# Manifold.net
KiCad netlist of a schematic drawn in EAGLE
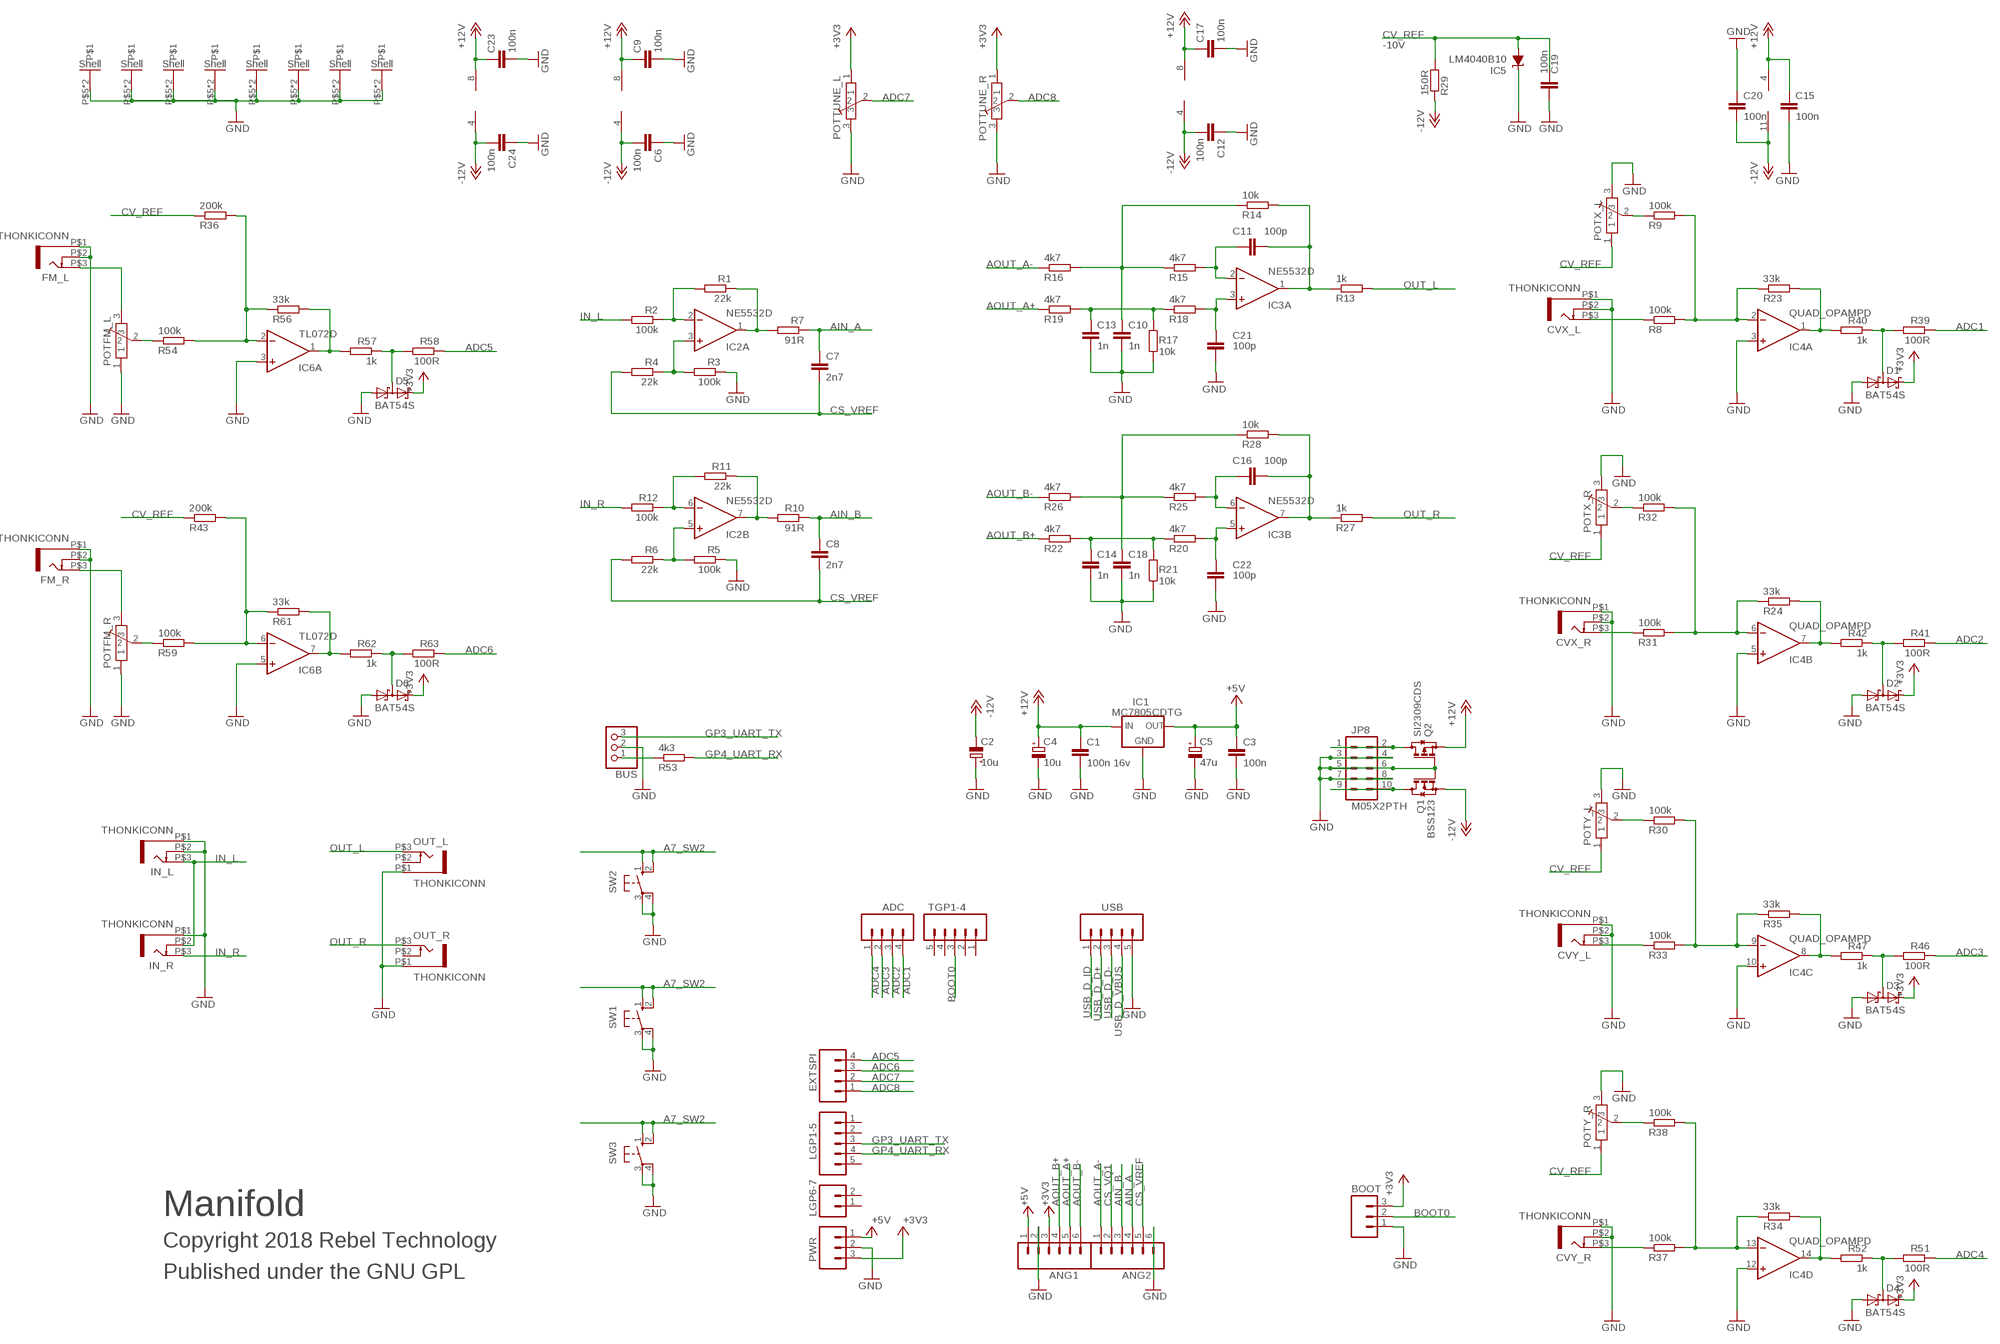
[diagram p0: schematic, sheet 1]

(export (version "E")
  (design (tool "Eeschema 10.0.6"))
  (components
    (comp (ref "ADC")
      (value "M04PTH")
      (footprint "eagle-import:1X04")
      (libsource (lib "eagle-import") (part "M04PTH"))
    )
    (comp (ref "ANG1")
      (value "M06SIP")
      (footprint "eagle-import:1X06")
      (libsource (lib "eagle-import") (part "M06SIP"))
    )
    (comp (ref "ANG2")
      (value "M06SIP")
      (footprint "eagle-import:1X06")
      (libsource (lib "eagle-import") (part "M06SIP"))
    )
    (comp (ref "BOOT")
      (value "M03PTH")
      (footprint "eagle-import:1X03")
      (libsource (lib "eagle-import") (part "M03PTH"))
    )
    (comp (ref "BUS")
      (value "CON-JST-1X03PH-TH")
      (footprint "eagle-import:JST-B3B-PH-KL")
      (libsource (lib "eagle-import") (part "CON-JST-1X03PH-TH"))
    )
    (comp (ref "C1")
      (value "100n 16v")
      (footprint "eagle-import:C0603")
      (libsource (lib "eagle-import") (part "C-EUC0603"))
    )
    (comp (ref "C2")
      (value "10u")
      (footprint "eagle-import:CPOL-5")
      (libsource (lib "eagle-import") (part "CPOL-EU153CLV-0505"))
    )
    (comp (ref "C3")
      (value "100n")
      (footprint "eagle-import:C0603")
      (libsource (lib "eagle-import") (part "C-EUC0603"))
    )
    (comp (ref "C4")
      (value "10u")
      (footprint "eagle-import:CPOL-5")
      (libsource (lib "eagle-import") (part "CPOL-EU153CLV-0505"))
    )
    (comp (ref "C5")
      (value "47u")
      (footprint "eagle-import:PANASONIC_C")
      (libsource (lib "eagle-import") (part "rcl_CPOL-EUC"))
    )
    (comp (ref "C6")
      (value "100n")
      (footprint "eagle-import:C0603")
      (libsource (lib "eagle-import") (part "resistor_C-EUC0603"))
    )
    (comp (ref "C7")
      (value "2n7")
      (footprint "eagle-import:C0603")
      (libsource (lib "eagle-import") (part "resistor_C-EUC0603"))
    )
    (comp (ref "C8")
      (value "2n7")
      (footprint "eagle-import:C0603")
      (libsource (lib "eagle-import") (part "resistor_C-EUC0603"))
    )
    (comp (ref "C9")
      (value "100n")
      (footprint "eagle-import:C0603")
      (libsource (lib "eagle-import") (part "resistor_C-EUC0603"))
    )
    (comp (ref "C10")
      (value "1n")
      (footprint "eagle-import:C0603")
      (libsource (lib "eagle-import") (part "resistor_C-EUC0603"))
    )
    (comp (ref "C11")
      (value "100p")
      (footprint "eagle-import:C0603")
      (libsource (lib "eagle-import") (part "resistor_C-EUC0603"))
    )
    (comp (ref "C12")
      (value "100n")
      (footprint "eagle-import:C0603")
      (libsource (lib "eagle-import") (part "resistor_C-EUC0603"))
    )
    (comp (ref "C13")
      (value "1n")
      (footprint "eagle-import:C0603")
      (libsource (lib "eagle-import") (part "resistor_C-EUC0603"))
    )
    (comp (ref "C14")
      (value "1n")
      (footprint "eagle-import:C0603")
      (libsource (lib "eagle-import") (part "resistor_C-EUC0603"))
    )
    (comp (ref "C15")
      (value "100n")
      (footprint "eagle-import:C0603")
      (libsource (lib "eagle-import") (part "resistor_C-EUC0603"))
    )
    (comp (ref "C16")
      (value "100p")
      (footprint "eagle-import:C0603")
      (libsource (lib "eagle-import") (part "resistor_C-EUC0603"))
    )
    (comp (ref "C17")
      (value "100n")
      (footprint "eagle-import:C0603")
      (libsource (lib "eagle-import") (part "resistor_C-EUC0603"))
    )
    (comp (ref "C18")
      (value "1n")
      (footprint "eagle-import:C0603")
      (libsource (lib "eagle-import") (part "resistor_C-EUC0603"))
    )
    (comp (ref "C19")
      (value "100n")
      (footprint "eagle-import:C0603")
      (libsource (lib "eagle-import") (part "resistor_C-EUC0603"))
    )
    (comp (ref "C20")
      (value "100n")
      (footprint "eagle-import:C0603")
      (libsource (lib "eagle-import") (part "resistor_C-EUC0603"))
    )
    (comp (ref "C21")
      (value "100p")
      (footprint "eagle-import:C0603")
      (libsource (lib "eagle-import") (part "resistor_C-EUC0603"))
    )
    (comp (ref "C22")
      (value "100p")
      (footprint "eagle-import:C0603")
      (libsource (lib "eagle-import") (part "resistor_C-EUC0603"))
    )
    (comp (ref "C23")
      (value "100n")
      (footprint "eagle-import:C0603")
      (libsource (lib "eagle-import") (part "resistor_C-EUC0603"))
    )
    (comp (ref "C24")
      (value "100n")
      (footprint "eagle-import:C0603")
      (libsource (lib "eagle-import") (part "resistor_C-EUC0603"))
    )
    (comp (ref "CVX_L")
      (value "THONKICONN")
      (footprint "eagle-import:THONKICONN")
      (libsource (lib "eagle-import") (part "THONKICONN"))
    )
    (comp (ref "CVX_R")
      (value "THONKICONN")
      (footprint "eagle-import:THONKICONN")
      (libsource (lib "eagle-import") (part "THONKICONN"))
    )
    (comp (ref "CVY_L")
      (value "THONKICONN")
      (footprint "eagle-import:THONKICONN")
      (libsource (lib "eagle-import") (part "THONKICONN"))
    )
    (comp (ref "CVY_R")
      (value "THONKICONN")
      (footprint "eagle-import:THONKICONN")
      (libsource (lib "eagle-import") (part "THONKICONN"))
    )
    (comp (ref "D1")
      (value "BAT54S")
      (footprint "eagle-import:SOT23")
      (libsource (lib "eagle-import") (part "BAT54S"))
    )
    (comp (ref "D2")
      (value "BAT54S")
      (footprint "eagle-import:SOT23")
      (libsource (lib "eagle-import") (part "BAT54S"))
    )
    (comp (ref "D3")
      (value "BAT54S")
      (footprint "eagle-import:SOT23")
      (libsource (lib "eagle-import") (part "BAT54S"))
    )
    (comp (ref "D4")
      (value "BAT54S")
      (footprint "eagle-import:SOT23")
      (libsource (lib "eagle-import") (part "BAT54S"))
    )
    (comp (ref "D5")
      (value "BAT54S")
      (footprint "eagle-import:SOT23")
      (libsource (lib "eagle-import") (part "BAT54S"))
    )
    (comp (ref "D6")
      (value "BAT54S")
      (footprint "eagle-import:SOT23")
      (libsource (lib "eagle-import") (part "BAT54S"))
    )
    (comp (ref "EXTSPI")
      (value "M04PTH")
      (footprint "eagle-import:1X04")
      (libsource (lib "eagle-import") (part "M04PTH"))
    )
    (comp (ref "FM_L")
      (value "THONKICONN")
      (footprint "eagle-import:THONKICONN")
      (libsource (lib "eagle-import") (part "THONKICONN"))
    )
    (comp (ref "FM_R")
      (value "THONKICONN")
      (footprint "eagle-import:THONKICONN")
      (libsource (lib "eagle-import") (part "THONKICONN"))
    )
    (comp (ref "IC1")
      (value "MC7805CDTG")
      (footprint "eagle-import:DPACK")
      (libsource (lib "eagle-import") (part "MC78XX"))
    )
    (comp (ref "IC2")
      (value "NE5532D")
      (footprint "eagle-import:SO08")
      (libsource (lib "eagle-import") (part "NE5532D"))
    )
    (comp (ref "IC3")
      (value "NE5532D")
      (footprint "eagle-import:SO08")
      (libsource (lib "eagle-import") (part "NE5532D"))
    )
    (comp (ref "IC4")
      (value "QUAD_OPAMPD")
      (footprint "eagle-import:SO14")
      (libsource (lib "eagle-import") (part "QUAD_OPAMPD"))
    )
    (comp (ref "IC5")
      (value "LM4040B10")
      (footprint "eagle-import:DBZ_R-PDSO-G3")
      (fields (field (name "MF") "TEXAS INSTRUMENT CONNECTORS") (field (name "MPN") "LM4041C12QDBZT"))
      (libsource (lib "eagle-import") (part "LM4041DBZC12"))
    )
    (comp (ref "IC6")
      (value "TL072D")
      (footprint "eagle-import:SO08")
      (libsource (lib "eagle-import") (part "TL072D"))
    )
    (comp (ref "IN_L")
      (value "THONKICONN")
      (footprint "eagle-import:THONKICONN")
      (libsource (lib "eagle-import") (part "THONKICONN"))
    )
    (comp (ref "IN_R")
      (value "THONKICONN")
      (footprint "eagle-import:THONKICONN")
      (libsource (lib "eagle-import") (part "THONKICONN"))
    )
    (comp (ref "JP8")
      (value "M05X2PTH")
      (footprint "eagle-import:AVR_ICSP")
      (libsource (lib "eagle-import") (part "M05X2PTH"))
    )
    (comp (ref "LGP1-5")
      (value "M05PTH")
      (footprint "eagle-import:1X05")
      (libsource (lib "eagle-import") (part "M05PTH"))
    )
    (comp (ref "LGP6-7")
      (value "M02PTH")
      (footprint "eagle-import:1X02")
      (libsource (lib "eagle-import") (part "M02PTH"))
    )
    (comp (ref "OUT_L")
      (value "THONKICONN")
      (footprint "eagle-import:THONKICONN")
      (libsource (lib "eagle-import") (part "THONKICONN"))
    )
    (comp (ref "OUT_R")
      (value "THONKICONN")
      (footprint "eagle-import:THONKICONN")
      (libsource (lib "eagle-import") (part "THONKICONN"))
    )
    (comp (ref "POTFM_L")
      (value "POT-ALPS-RK09L1140")
      (footprint "eagle-import:POT-ALPS-RK09L1140")
      (libsource (lib "eagle-import") (part "POT-ALPS-RK09L1140"))
    )
    (comp (ref "POTFM_R")
      (value "POT-ALPS-RK09L1140")
      (footprint "eagle-import:POT-ALPS-RK09L1140")
      (libsource (lib "eagle-import") (part "POT-ALPS-RK09L1140"))
    )
    (comp (ref "POTTUNE_L")
      (value "POT-ALPS-RK09L1140")
      (footprint "eagle-import:POT-ALPS-RK09L1140")
      (libsource (lib "eagle-import") (part "POT-ALPS-RK09L1140"))
    )
    (comp (ref "POTTUNE_R")
      (value "POT-ALPS-RK09L1140")
      (footprint "eagle-import:POT-ALPS-RK09L1140")
      (libsource (lib "eagle-import") (part "POT-ALPS-RK09L1140"))
    )
    (comp (ref "POTX_L")
      (value "POT-ALPS-RK09L1140")
      (footprint "eagle-import:POT-ALPS-RK09L1140")
      (libsource (lib "eagle-import") (part "POT-ALPS-RK09L1140"))
    )
    (comp (ref "POTX_R")
      (value "POT-ALPS-RK09L1140")
      (footprint "eagle-import:POT-ALPS-RK09L1140")
      (libsource (lib "eagle-import") (part "POT-ALPS-RK09L1140"))
    )
    (comp (ref "POTY_L")
      (value "POT-ALPS-RK09L1140")
      (footprint "eagle-import:POT-ALPS-RK09L1140")
      (libsource (lib "eagle-import") (part "POT-ALPS-RK09L1140"))
    )
    (comp (ref "POTY_R")
      (value "POT-ALPS-RK09L1140")
      (footprint "eagle-import:POT-ALPS-RK09L1140")
      (libsource (lib "eagle-import") (part "POT-ALPS-RK09L1140"))
    )
    (comp (ref "PWR")
      (value "M03PTH")
      (footprint "eagle-import:1X03")
      (libsource (lib "eagle-import") (part "M03PTH"))
    )
    (comp (ref "Q1")
      (value "BSS123")
      (footprint "eagle-import:SOT23")
      (libsource (lib "eagle-import") (part "BSS123"))
    )
    (comp (ref "Q2")
      (value "SI2309CDS")
      (footprint "eagle-import:SOT23")
      (libsource (lib "eagle-import") (part "BSS84"))
    )
    (comp (ref "R1")
      (value "22k")
      (footprint "eagle-import:0603")
      (libsource (lib "eagle-import") (part "R-EU_0603"))
    )
    (comp (ref "R2")
      (value "100k")
      (footprint "eagle-import:0603")
      (libsource (lib "eagle-import") (part "R-EU_0603"))
    )
    (comp (ref "R3")
      (value "100k")
      (footprint "eagle-import:0603")
      (libsource (lib "eagle-import") (part "R-EU_0603"))
    )
    (comp (ref "R4")
      (value "22k")
      (footprint "eagle-import:0603")
      (libsource (lib "eagle-import") (part "R-EU_0603"))
    )
    (comp (ref "R5")
      (value "100k")
      (footprint "eagle-import:0603")
      (libsource (lib "eagle-import") (part "R-EU_0603"))
    )
    (comp (ref "R6")
      (value "22k")
      (footprint "eagle-import:0603")
      (libsource (lib "eagle-import") (part "R-EU_0603"))
    )
    (comp (ref "R7")
      (value "91R")
      (footprint "eagle-import:0603")
      (libsource (lib "eagle-import") (part "R-EU_0603"))
    )
    (comp (ref "R8")
      (value "100k")
      (footprint "eagle-import:0603")
      (libsource (lib "eagle-import") (part "R-EU_0603"))
    )
    (comp (ref "R9")
      (value "100k")
      (footprint "eagle-import:0603")
      (libsource (lib "eagle-import") (part "R-EU_0603"))
    )
    (comp (ref "R10")
      (value "91R")
      (footprint "eagle-import:0603")
      (libsource (lib "eagle-import") (part "R-EU_0603"))
    )
    (comp (ref "R11")
      (value "22k")
      (footprint "eagle-import:0603")
      (libsource (lib "eagle-import") (part "R-EU_0603"))
    )
    (comp (ref "R12")
      (value "100k")
      (footprint "eagle-import:0603")
      (libsource (lib "eagle-import") (part "R-EU_0603"))
    )
    (comp (ref "R13")
      (value "1k")
      (footprint "eagle-import:0603")
      (libsource (lib "eagle-import") (part "R-EU_0603"))
    )
    (comp (ref "R14")
      (value "10k")
      (footprint "eagle-import:0603")
      (libsource (lib "eagle-import") (part "R-EU_0603"))
    )
    (comp (ref "R15")
      (value "4k7")
      (footprint "eagle-import:0603")
      (libsource (lib "eagle-import") (part "R-EU_0603"))
    )
    (comp (ref "R16")
      (value "4k7")
      (footprint "eagle-import:0603")
      (libsource (lib "eagle-import") (part "R-EU_0603"))
    )
    (comp (ref "R17")
      (value "10k")
      (footprint "eagle-import:0603")
      (libsource (lib "eagle-import") (part "R-EU_0603"))
    )
    (comp (ref "R18")
      (value "4k7")
      (footprint "eagle-import:0603")
      (libsource (lib "eagle-import") (part "R-EU_0603"))
    )
    (comp (ref "R19")
      (value "4k7")
      (footprint "eagle-import:0603")
      (libsource (lib "eagle-import") (part "R-EU_0603"))
    )
    (comp (ref "R20")
      (value "4k7")
      (footprint "eagle-import:0603")
      (libsource (lib "eagle-import") (part "R-EU_0603"))
    )
    (comp (ref "R21")
      (value "10k")
      (footprint "eagle-import:0603")
      (libsource (lib "eagle-import") (part "R-EU_0603"))
    )
    (comp (ref "R22")
      (value "4k7")
      (footprint "eagle-import:0603")
      (libsource (lib "eagle-import") (part "R-EU_0603"))
    )
    (comp (ref "R23")
      (value "33k")
      (footprint "eagle-import:0603")
      (libsource (lib "eagle-import") (part "R-EU_0603"))
    )
    (comp (ref "R24")
      (value "33k")
      (footprint "eagle-import:0603")
      (libsource (lib "eagle-import") (part "R-EU_0603"))
    )
    (comp (ref "R25")
      (value "4k7")
      (footprint "eagle-import:0603")
      (libsource (lib "eagle-import") (part "R-EU_0603"))
    )
    (comp (ref "R26")
      (value "4k7")
      (footprint "eagle-import:0603")
      (libsource (lib "eagle-import") (part "R-EU_0603"))
    )
    (comp (ref "R27")
      (value "1k")
      (footprint "eagle-import:0603")
      (libsource (lib "eagle-import") (part "R-EU_0603"))
    )
    (comp (ref "R28")
      (value "10k")
      (footprint "eagle-import:0603")
      (libsource (lib "eagle-import") (part "R-EU_0603"))
    )
    (comp (ref "R29")
      (value "150R")
      (footprint "eagle-import:0603")
      (libsource (lib "eagle-import") (part "R-EU_0603"))
    )
    (comp (ref "R30")
      (value "100k")
      (footprint "eagle-import:0603")
      (libsource (lib "eagle-import") (part "R-EU_0603"))
    )
    (comp (ref "R31")
      (value "100k")
      (footprint "eagle-import:0603")
      (libsource (lib "eagle-import") (part "R-EU_0603"))
    )
    (comp (ref "R32")
      (value "100k")
      (footprint "eagle-import:0603")
      (libsource (lib "eagle-import") (part "R-EU_0603"))
    )
    (comp (ref "R33")
      (value "100k")
      (footprint "eagle-import:0603")
      (libsource (lib "eagle-import") (part "R-EU_0603"))
    )
    (comp (ref "R34")
      (value "33k")
      (footprint "eagle-import:0603")
      (libsource (lib "eagle-import") (part "R-EU_0603"))
    )
    (comp (ref "R35")
      (value "33k")
      (footprint "eagle-import:0603")
      (libsource (lib "eagle-import") (part "R-EU_0603"))
    )
    (comp (ref "R36")
      (value "200k")
      (footprint "eagle-import:0603")
      (libsource (lib "eagle-import") (part "R-EU_0603"))
    )
    (comp (ref "R37")
      (value "100k")
      (footprint "eagle-import:0603")
      (libsource (lib "eagle-import") (part "R-EU_0603"))
    )
    (comp (ref "R38")
      (value "100k")
      (footprint "eagle-import:0603")
      (libsource (lib "eagle-import") (part "R-EU_0603"))
    )
    (comp (ref "R39")
      (value "100R")
      (footprint "eagle-import:0603")
      (libsource (lib "eagle-import") (part "R-EU_0603"))
    )
    (comp (ref "R40")
      (value "1k")
      (footprint "eagle-import:0603")
      (libsource (lib "eagle-import") (part "R-EU_0603"))
    )
    (comp (ref "R41")
      (value "100R")
      (footprint "eagle-import:0603")
      (libsource (lib "eagle-import") (part "R-EU_0603"))
    )
    (comp (ref "R42")
      (value "1k")
      (footprint "eagle-import:0603")
      (libsource (lib "eagle-import") (part "R-EU_0603"))
    )
    (comp (ref "R43")
      (value "200k")
      (footprint "eagle-import:0603")
      (libsource (lib "eagle-import") (part "R-EU_0603"))
    )
    (comp (ref "R46")
      (value "100R")
      (footprint "eagle-import:0603")
      (libsource (lib "eagle-import") (part "R-EU_0603"))
    )
    (comp (ref "R47")
      (value "1k")
      (footprint "eagle-import:0603")
      (libsource (lib "eagle-import") (part "R-EU_0603"))
    )
    (comp (ref "R51")
      (value "100R")
      (footprint "eagle-import:0603")
      (libsource (lib "eagle-import") (part "R-EU_0603"))
    )
    (comp (ref "R52")
      (value "1k")
      (footprint "eagle-import:0603")
      (libsource (lib "eagle-import") (part "R-EU_0603"))
    )
    (comp (ref "R53")
      (value "4k3")
      (footprint "eagle-import:0603")
      (libsource (lib "eagle-import") (part "R-EU_0603"))
    )
    (comp (ref "R54")
      (value "100k")
      (footprint "eagle-import:0603")
      (libsource (lib "eagle-import") (part "R-EU_0603"))
    )
    (comp (ref "R56")
      (value "33k")
      (footprint "eagle-import:0603")
      (libsource (lib "eagle-import") (part "R-EU_0603"))
    )
    (comp (ref "R57")
      (value "1k")
      (footprint "eagle-import:0603")
      (libsource (lib "eagle-import") (part "R-EU_0603"))
    )
    (comp (ref "R58")
      (value "100R")
      (footprint "eagle-import:0603")
      (libsource (lib "eagle-import") (part "R-EU_0603"))
    )
    (comp (ref "R59")
      (value "100k")
      (footprint "eagle-import:0603")
      (libsource (lib "eagle-import") (part "R-EU_0603"))
    )
    (comp (ref "R61")
      (value "33k")
      (footprint "eagle-import:0603")
      (libsource (lib "eagle-import") (part "R-EU_0603"))
    )
    (comp (ref "R62")
      (value "1k")
      (footprint "eagle-import:0603")
      (libsource (lib "eagle-import") (part "R-EU_0603"))
    )
    (comp (ref "R63")
      (value "100R")
      (footprint "eagle-import:0603")
      (libsource (lib "eagle-import") (part "R-EU_0603"))
    )
    (comp (ref "SW1")
      (value "10-XX")
      (footprint "eagle-import:B3F-10XX")
      (fields (field (name "MPN") "B3F-1000"))
      (libsource (lib "eagle-import") (part "10-XX"))
    )
    (comp (ref "SW2")
      (value "10-XX")
      (footprint "eagle-import:B3F-10XX")
      (fields (field (name "MPN") "B3F-1000"))
      (libsource (lib "eagle-import") (part "10-XX"))
    )
    (comp (ref "SW3")
      (value "10-XX")
      (footprint "eagle-import:B3F-10XX")
      (fields (field (name "MPN") "B3F-1000"))
      (libsource (lib "eagle-import") (part "10-XX"))
    )
    (comp (ref "TGP1-4")
      (value "M05PTH")
      (footprint "eagle-import:1X05")
      (libsource (lib "eagle-import") (part "M05PTH"))
    )
    (comp (ref "USB")
      (value "M05PTH")
      (footprint "eagle-import:1X05")
      (libsource (lib "eagle-import") (part "M05PTH"))
    )
  )
  (nets
    (net (code "1") (name "+3V3") (class "Default")
      (node (ref "ANG1") (pin "3") (pinfunction "3_3") (pintype "passive"))
      (node (ref "BOOT") (pin "3") (pinfunction "3_3") (pintype "passive"))
      (node (ref "D1") (pin "2") (pinfunction "C2_2") (pintype "passive"))
      (node (ref "D2") (pin "2") (pinfunction "C2_2") (pintype "passive"))
      (node (ref "D3") (pin "2") (pinfunction "C2_2") (pintype "passive"))
      (node (ref "D4") (pin "2") (pinfunction "C2_2") (pintype "passive"))
      (node (ref "D5") (pin "2") (pinfunction "C2_2") (pintype "passive"))
      (node (ref "D6") (pin "2") (pinfunction "C2_2") (pintype "passive"))
      (node (ref "POTTUNE_L") (pin "1") (pinfunction "1_1") (pintype "bidirectional"))
      (node (ref "POTTUNE_R") (pin "1") (pinfunction "1_1") (pintype "bidirectional"))
      (node (ref "PWR") (pin "3") (pinfunction "3_3") (pintype "passive"))
    )
    (net (code "2") (name "+5V") (class "Default")
      (node (ref "ANG1") (pin "1") (pinfunction "1_1") (pintype "passive"))
      (node (ref "C3") (pin "1") (pinfunction "1_1") (pintype "passive"))
      (node (ref "C5") (pin "+") (pinfunction "+_+") (pintype "passive"))
      (node (ref "IC1") (pin "3") (pinfunction "OUT_3") (pintype "passive"))
      (node (ref "PWR") (pin "1") (pinfunction "1_1") (pintype "passive"))
    )
    (net (code "3") (name "+12V") (class "Default")
      (node (ref "C1") (pin "1") (pinfunction "1_1") (pintype "passive"))
      (node (ref "C15") (pin "1") (pinfunction "1_1") (pintype "passive"))
      (node (ref "C17") (pin "1") (pinfunction "1_1") (pintype "passive"))
      (node (ref "C23") (pin "1") (pinfunction "1_1") (pintype "passive"))
      (node (ref "C4") (pin "+") (pinfunction "+_+") (pintype "passive"))
      (node (ref "C9") (pin "1") (pinfunction "1_1") (pintype "passive"))
      (node (ref "IC1") (pin "1") (pinfunction "IN_1") (pintype "input"))
      (node (ref "IC2") (pin "8") (pinfunction "V+_8") (pintype "power_in"))
      (node (ref "IC3") (pin "8") (pinfunction "V+_8") (pintype "power_in"))
      (node (ref "IC4") (pin "4") (pinfunction "V+_4") (pintype "power_in"))
      (node (ref "IC6") (pin "8") (pinfunction "V+_8") (pintype "power_in"))
      (node (ref "Q2") (pin "2") (pinfunction "S_2") (pintype "passive"))
    )
    (net (code "4") (name "-12V") (class "Default")
      (node (ref "C12") (pin "2") (pinfunction "2_2") (pintype "passive"))
      (node (ref "C2") (pin "-") (pinfunction "-_-") (pintype "passive"))
      (node (ref "C20") (pin "2") (pinfunction "2_2") (pintype "passive"))
      (node (ref "C24") (pin "2") (pinfunction "2_2") (pintype "passive"))
      (node (ref "C6") (pin "2") (pinfunction "2_2") (pintype "passive"))
      (node (ref "IC2") (pin "4") (pinfunction "V-_4") (pintype "power_in"))
      (node (ref "IC3") (pin "4") (pinfunction "V-_4") (pintype "power_in"))
      (node (ref "IC4") (pin "11") (pinfunction "V-_11") (pintype "power_in"))
      (node (ref "IC6") (pin "4") (pinfunction "V-_4") (pintype "power_in"))
      (node (ref "Q1") (pin "2") (pinfunction "S_2") (pintype "passive"))
      (node (ref "R29") (pin "1") (pinfunction "1_1") (pintype "passive"))
    )
    (net (code "5") (name "/A7_SW2") (class "Default")
      (node (ref "SW1") (pin "1") (pinfunction "S_1") (pintype "passive"))
      (node (ref "SW1") (pin "2") (pinfunction "S1_2") (pintype "passive"))
      (node (ref "SW2") (pin "1") (pinfunction "S_1") (pintype "passive"))
      (node (ref "SW2") (pin "2") (pinfunction "S1_2") (pintype "passive"))
      (node (ref "SW3") (pin "1") (pinfunction "S_1") (pintype "passive"))
      (node (ref "SW3") (pin "2") (pinfunction "S1_2") (pintype "passive"))
    )
    (net (code "6") (name "/ADC1") (class "Default")
      (node (ref "ADC") (pin "4") (pinfunction "4_4") (pintype "passive"))
      (node (ref "R39") (pin "1") (pinfunction "1_1") (pintype "passive"))
    )
    (net (code "7") (name "/ADC2") (class "Default")
      (node (ref "ADC") (pin "3") (pinfunction "3_3") (pintype "passive"))
      (node (ref "R41") (pin "1") (pinfunction "1_1") (pintype "passive"))
    )
    (net (code "8") (name "/ADC3") (class "Default")
      (node (ref "ADC") (pin "2") (pinfunction "2_2") (pintype "passive"))
      (node (ref "R46") (pin "1") (pinfunction "1_1") (pintype "passive"))
    )
    (net (code "9") (name "/ADC4") (class "Default")
      (node (ref "ADC") (pin "1") (pinfunction "1_1") (pintype "passive"))
      (node (ref "R51") (pin "1") (pinfunction "1_1") (pintype "passive"))
    )
    (net (code "10") (name "/ADC5") (class "Default")
      (node (ref "EXTSPI") (pin "4") (pinfunction "4_4") (pintype "passive"))
      (node (ref "R58") (pin "1") (pinfunction "1_1") (pintype "passive"))
    )
    (net (code "11") (name "/ADC6") (class "Default")
      (node (ref "EXTSPI") (pin "3") (pinfunction "3_3") (pintype "passive"))
      (node (ref "R63") (pin "1") (pinfunction "1_1") (pintype "passive"))
    )
    (net (code "12") (name "/ADC7") (class "Default")
      (node (ref "EXTSPI") (pin "2") (pinfunction "2_2") (pintype "passive"))
      (node (ref "POTTUNE_L") (pin "2") (pinfunction "2_2") (pintype "bidirectional"))
    )
    (net (code "13") (name "/ADC8") (class "Default")
      (node (ref "EXTSPI") (pin "1") (pinfunction "1_1") (pintype "passive"))
      (node (ref "POTTUNE_R") (pin "2") (pinfunction "2_2") (pintype "bidirectional"))
    )
    (net (code "14") (name "/AIN_A") (class "Default")
      (node (ref "ANG2") (pin "4") (pinfunction "4_4") (pintype "passive"))
      (node (ref "C7") (pin "1") (pinfunction "1_1") (pintype "passive"))
      (node (ref "R7") (pin "1") (pinfunction "1_1") (pintype "passive"))
    )
    (net (code "15") (name "/AIN_B") (class "Default")
      (node (ref "ANG2") (pin "3") (pinfunction "3_3") (pintype "passive"))
      (node (ref "C8") (pin "1") (pinfunction "1_1") (pintype "passive"))
      (node (ref "R10") (pin "1") (pinfunction "1_1") (pintype "passive"))
    )
    (net (code "16") (name "/AOUT_A+") (class "Default")
      (node (ref "ANG1") (pin "5") (pinfunction "5_5") (pintype "passive"))
      (node (ref "R19") (pin "1") (pinfunction "1_1") (pintype "passive"))
    )
    (net (code "17") (name "/AOUT_A-") (class "Default")
      (node (ref "ANG2") (pin "1") (pinfunction "1_1") (pintype "passive"))
      (node (ref "R16") (pin "1") (pinfunction "1_1") (pintype "passive"))
    )
    (net (code "18") (name "/AOUT_B+") (class "Default")
      (node (ref "ANG1") (pin "4") (pinfunction "4_4") (pintype "passive"))
      (node (ref "R22") (pin "1") (pinfunction "1_1") (pintype "passive"))
    )
    (net (code "19") (name "/AOUT_B-") (class "Default")
      (node (ref "ANG1") (pin "6") (pinfunction "6_6") (pintype "passive"))
      (node (ref "R26") (pin "1") (pinfunction "1_1") (pintype "passive"))
    )
    (net (code "20") (name "/BOOT0") (class "Default")
      (node (ref "BOOT") (pin "2") (pinfunction "2_2") (pintype "passive"))
      (node (ref "TGP1-4") (pin "3") (pinfunction "3_3") (pintype "passive"))
    )
    (net (code "21") (name "/CS_VQ1") (class "Default")
      (node (ref "ANG2") (pin "2") (pinfunction "2_2") (pintype "passive"))
    )
    (net (code "22") (name "/CS_VREF") (class "Default")
      (node (ref "ANG2") (pin "5") (pinfunction "5_5") (pintype "passive"))
      (node (ref "C7") (pin "2") (pinfunction "2_2") (pintype "passive"))
      (node (ref "C8") (pin "2") (pinfunction "2_2") (pintype "passive"))
      (node (ref "R4") (pin "2") (pinfunction "2_2") (pintype "passive"))
      (node (ref "R6") (pin "2") (pinfunction "2_2") (pintype "passive"))
    )
    (net (code "23") (name "/CV_REF") (class "Default")
      (node (ref "C19") (pin "1") (pinfunction "1_1") (pintype "passive"))
      (node (ref "IC5") (pin "2") (pinfunction "A_2") (pintype "passive"))
      (node (ref "POTX_L") (pin "1") (pinfunction "1_1") (pintype "bidirectional"))
      (node (ref "POTX_R") (pin "1") (pinfunction "1_1") (pintype "bidirectional"))
      (node (ref "POTY_L") (pin "1") (pinfunction "1_1") (pintype "bidirectional"))
      (node (ref "POTY_R") (pin "1") (pinfunction "1_1") (pintype "bidirectional"))
      (node (ref "R29") (pin "2") (pinfunction "2_2") (pintype "passive"))
      (node (ref "R36") (pin "1") (pinfunction "1_1") (pintype "passive"))
      (node (ref "R43") (pin "1") (pinfunction "1_1") (pintype "passive"))
    )
    (net (code "24") (name "/GP3_UART_TX") (class "Default")
      (node (ref "BUS") (pin "3") (pinfunction "3_3") (pintype "passive"))
      (node (ref "LGP1-5") (pin "3") (pinfunction "3_3") (pintype "passive"))
    )
    (net (code "25") (name "/GP4_UART_RX") (class "Default")
      (node (ref "LGP1-5") (pin "4") (pinfunction "4_4") (pintype "passive"))
      (node (ref "R53") (pin "2") (pinfunction "2_2") (pintype "passive"))
    )
    (net (code "26") (name "/IN_L") (class "Default")
      (node (ref "IN_L") (pin "P$3") (pinfunction "3_P$3") (pintype "passive"))
      (node (ref "IN_R") (pin "P$2") (pinfunction "4_P$2") (pintype "passive"))
      (node (ref "R2") (pin "2") (pinfunction "2_2") (pintype "passive"))
    )
    (net (code "27") (name "/IN_R") (class "Default")
      (node (ref "IN_R") (pin "P$3") (pinfunction "3_P$3") (pintype "passive"))
      (node (ref "R12") (pin "2") (pinfunction "2_2") (pintype "passive"))
    )
    (net (code "28") (name "/OUT_L") (class "Default")
      (node (ref "OUT_L") (pin "P$3") (pinfunction "3_P$3") (pintype "passive"))
      (node (ref "R13") (pin "2") (pinfunction "2_2") (pintype "passive"))
    )
    (net (code "29") (name "/OUT_R") (class "Default")
      (node (ref "OUT_R") (pin "P$3") (pinfunction "3_P$3") (pintype "passive"))
      (node (ref "R27") (pin "2") (pinfunction "2_2") (pintype "passive"))
    )
    (net (code "30") (name "/USB_D_D+") (class "Default")
      (node (ref "USB") (pin "2") (pinfunction "2_2") (pintype "passive"))
    )
    (net (code "31") (name "/USB_D_D-") (class "Default")
      (node (ref "USB") (pin "3") (pinfunction "3_3") (pintype "passive"))
    )
    (net (code "32") (name "/USB_D_ID") (class "Default")
      (node (ref "USB") (pin "1") (pinfunction "1_1") (pintype "passive"))
    )
    (net (code "33") (name "/USB_D_VBUS") (class "Default")
      (node (ref "USB") (pin "4") (pinfunction "4_4") (pintype "passive"))
    )
    (net (code "34") (name "GND") (class "Default")
      (node (ref "ANG1") (pin "2") (pinfunction "2_2") (pintype "passive"))
      (node (ref "ANG2") (pin "6") (pinfunction "6_6") (pintype "passive"))
      (node (ref "BOOT") (pin "1") (pinfunction "1_1") (pintype "passive"))
      (node (ref "BUS") (pin "2") (pinfunction "2_2") (pintype "passive"))
      (node (ref "C1") (pin "2") (pinfunction "2_2") (pintype "passive"))
      (node (ref "C10") (pin "2") (pinfunction "2_2") (pintype "passive"))
      (node (ref "C12") (pin "1") (pinfunction "1_1") (pintype "passive"))
      (node (ref "C13") (pin "2") (pinfunction "2_2") (pintype "passive"))
      (node (ref "C14") (pin "2") (pinfunction "2_2") (pintype "passive"))
      (node (ref "C15") (pin "2") (pinfunction "2_2") (pintype "passive"))
      (node (ref "C17") (pin "2") (pinfunction "2_2") (pintype "passive"))
      (node (ref "C18") (pin "2") (pinfunction "2_2") (pintype "passive"))
      (node (ref "C19") (pin "2") (pinfunction "2_2") (pintype "passive"))
      (node (ref "C2") (pin "+") (pinfunction "+_+") (pintype "passive"))
      (node (ref "C20") (pin "1") (pinfunction "1_1") (pintype "passive"))
      (node (ref "C21") (pin "2") (pinfunction "2_2") (pintype "passive"))
      (node (ref "C22") (pin "2") (pinfunction "2_2") (pintype "passive"))
      (node (ref "C23") (pin "2") (pinfunction "2_2") (pintype "passive"))
      (node (ref "C24") (pin "1") (pinfunction "1_1") (pintype "passive"))
      (node (ref "C3") (pin "2") (pinfunction "2_2") (pintype "passive"))
      (node (ref "C4") (pin "-") (pinfunction "-_-") (pintype "passive"))
      (node (ref "C5") (pin "-") (pinfunction "-_-") (pintype "passive"))
      (node (ref "C6") (pin "1") (pinfunction "1_1") (pintype "passive"))
      (node (ref "C9") (pin "2") (pinfunction "2_2") (pintype "passive"))
      (node (ref "CVX_L") (pin "P$1") (pinfunction "5_P$1") (pintype "passive"))
      (node (ref "CVX_L") (pin "P$2") (pinfunction "4_P$2") (pintype "passive"))
      (node (ref "CVX_R") (pin "P$1") (pinfunction "5_P$1") (pintype "passive"))
      (node (ref "CVX_R") (pin "P$2") (pinfunction "4_P$2") (pintype "passive"))
      (node (ref "CVY_L") (pin "P$1") (pinfunction "5_P$1") (pintype "passive"))
      (node (ref "CVY_L") (pin "P$2") (pinfunction "4_P$2") (pintype "passive"))
      (node (ref "CVY_R") (pin "P$1") (pinfunction "5_P$1") (pintype "passive"))
      (node (ref "CVY_R") (pin "P$2") (pinfunction "4_P$2") (pintype "passive"))
      (node (ref "D1") (pin "1") (pinfunction "A1_1") (pintype "passive"))
      (node (ref "D2") (pin "1") (pinfunction "A1_1") (pintype "passive"))
      (node (ref "D3") (pin "1") (pinfunction "A1_1") (pintype "passive"))
      (node (ref "D4") (pin "1") (pinfunction "A1_1") (pintype "passive"))
      (node (ref "D5") (pin "1") (pinfunction "A1_1") (pintype "passive"))
      (node (ref "D6") (pin "1") (pinfunction "A1_1") (pintype "passive"))
      (node (ref "FM_L") (pin "P$1") (pinfunction "5_P$1") (pintype "passive"))
      (node (ref "FM_L") (pin "P$2") (pinfunction "4_P$2") (pintype "passive"))
      (node (ref "FM_R") (pin "P$1") (pinfunction "5_P$1") (pintype "passive"))
      (node (ref "FM_R") (pin "P$2") (pinfunction "4_P$2") (pintype "passive"))
      (node (ref "IC1") (pin "4") (pinfunction "GND_4") (pintype "input"))
      (node (ref "IC4") (pin "10") (pinfunction "+IN_10") (pintype "input"))
      (node (ref "IC4") (pin "12") (pinfunction "+IN_12") (pintype "input"))
      (node (ref "IC4") (pin "3") (pinfunction "+IN_3") (pintype "input"))
      (node (ref "IC4") (pin "5") (pinfunction "+IN_5") (pintype "input"))
      (node (ref "IC5") (pin "1") (pinfunction "C_1") (pintype "passive"))
      (node (ref "IC6") (pin "3") (pinfunction "+IN_3") (pintype "input"))
      (node (ref "IC6") (pin "5") (pinfunction "+IN_5") (pintype "input"))
      (node (ref "IN_L") (pin "P$1") (pinfunction "5_P$1") (pintype "passive"))
      (node (ref "IN_L") (pin "P$2") (pinfunction "4_P$2") (pintype "passive"))
      (node (ref "IN_R") (pin "P$1") (pinfunction "5_P$1") (pintype "passive"))
      (node (ref "JP8") (pin "3") (pinfunction "3_3") (pintype "passive"))
      (node (ref "JP8") (pin "4") (pinfunction "4_4") (pintype "passive"))
      (node (ref "JP8") (pin "5") (pinfunction "5_5") (pintype "passive"))
      (node (ref "JP8") (pin "6") (pinfunction "6_6") (pintype "passive"))
      (node (ref "JP8") (pin "7") (pinfunction "7_7") (pintype "passive"))
      (node (ref "JP8") (pin "8") (pinfunction "8_8") (pintype "passive"))
      (node (ref "OUT_L") (pin "P$1") (pinfunction "5_P$1") (pintype "passive"))
      (node (ref "OUT_R") (pin "P$1") (pinfunction "5_P$1") (pintype "passive"))
      (node (ref "POTFM_L") (pin "1") (pinfunction "1_1") (pintype "bidirectional"))
      (node (ref "POTFM_L") (pin "P$5") (pinfunction "P$1_P$5") (pintype "bidirectional"))
      (node (ref "POTFM_L") (pin "P$6") (pinfunction "P$1_P$6") (pintype "bidirectional"))
      (node (ref "POTFM_R") (pin "1") (pinfunction "1_1") (pintype "bidirectional"))
      (node (ref "POTFM_R") (pin "P$5") (pinfunction "P$1_P$5") (pintype "bidirectional"))
      (node (ref "POTFM_R") (pin "P$6") (pinfunction "P$1_P$6") (pintype "bidirectional"))
      (node (ref "POTTUNE_L") (pin "3") (pinfunction "3_3") (pintype "bidirectional"))
      (node (ref "POTTUNE_L") (pin "P$5") (pinfunction "P$1_P$5") (pintype "bidirectional"))
      (node (ref "POTTUNE_L") (pin "P$6") (pinfunction "P$1_P$6") (pintype "bidirectional"))
      (node (ref "POTTUNE_R") (pin "3") (pinfunction "3_3") (pintype "bidirectional"))
      (node (ref "POTTUNE_R") (pin "P$5") (pinfunction "P$1_P$5") (pintype "bidirectional"))
      (node (ref "POTTUNE_R") (pin "P$6") (pinfunction "P$1_P$6") (pintype "bidirectional"))
      (node (ref "POTX_L") (pin "3") (pinfunction "3_3") (pintype "bidirectional"))
      (node (ref "POTX_L") (pin "P$5") (pinfunction "P$1_P$5") (pintype "bidirectional"))
      (node (ref "POTX_L") (pin "P$6") (pinfunction "P$1_P$6") (pintype "bidirectional"))
      (node (ref "POTX_R") (pin "3") (pinfunction "3_3") (pintype "bidirectional"))
      (node (ref "POTX_R") (pin "P$5") (pinfunction "P$1_P$5") (pintype "bidirectional"))
      (node (ref "POTX_R") (pin "P$6") (pinfunction "P$1_P$6") (pintype "bidirectional"))
      (node (ref "POTY_L") (pin "3") (pinfunction "3_3") (pintype "bidirectional"))
      (node (ref "POTY_L") (pin "P$5") (pinfunction "P$1_P$5") (pintype "bidirectional"))
      (node (ref "POTY_L") (pin "P$6") (pinfunction "P$1_P$6") (pintype "bidirectional"))
      (node (ref "POTY_R") (pin "3") (pinfunction "3_3") (pintype "bidirectional"))
      (node (ref "POTY_R") (pin "P$5") (pinfunction "P$1_P$5") (pintype "bidirectional"))
      (node (ref "POTY_R") (pin "P$6") (pinfunction "P$1_P$6") (pintype "bidirectional"))
      (node (ref "PWR") (pin "2") (pinfunction "2_2") (pintype "passive"))
      (node (ref "Q1") (pin "1") (pinfunction "G_1") (pintype "passive"))
      (node (ref "Q2") (pin "1") (pinfunction "G_1") (pintype "passive"))
      (node (ref "R17") (pin "1") (pinfunction "1_1") (pintype "passive"))
      (node (ref "R21") (pin "1") (pinfunction "1_1") (pintype "passive"))
      (node (ref "R3") (pin "1") (pinfunction "1_1") (pintype "passive"))
      (node (ref "R5") (pin "1") (pinfunction "1_1") (pintype "passive"))
      (node (ref "SW1") (pin "3") (pinfunction "P_3") (pintype "passive"))
      (node (ref "SW1") (pin "4") (pinfunction "P1_4") (pintype "passive"))
      (node (ref "SW2") (pin "3") (pinfunction "P_3") (pintype "passive"))
      (node (ref "SW2") (pin "4") (pinfunction "P1_4") (pintype "passive"))
      (node (ref "SW3") (pin "3") (pinfunction "P_3") (pintype "passive"))
      (node (ref "SW3") (pin "4") (pinfunction "P1_4") (pintype "passive"))
      (node (ref "USB") (pin "5") (pinfunction "5_5") (pintype "passive"))
    )
    (net (code "35") (name "Net-(BUS-Pad1)") (class "Default")
      (node (ref "BUS") (pin "1") (pinfunction "1_1") (pintype "passive"))
      (node (ref "R53") (pin "1") (pinfunction "1_1") (pintype "passive"))
    )
    (net (code "36") (name "Net-(C10-Pad1)") (class "Default")
      (node (ref "C10") (pin "1") (pinfunction "1_1") (pintype "passive"))
      (node (ref "R14") (pin "1") (pinfunction "1_1") (pintype "passive"))
      (node (ref "R15") (pin "1") (pinfunction "1_1") (pintype "passive"))
      (node (ref "R16") (pin "2") (pinfunction "2_2") (pintype "passive"))
    )
    (net (code "37") (name "Net-(C13-Pad1)") (class "Default")
      (node (ref "C13") (pin "1") (pinfunction "1_1") (pintype "passive"))
      (node (ref "R17") (pin "2") (pinfunction "2_2") (pintype "passive"))
      (node (ref "R18") (pin "1") (pinfunction "1_1") (pintype "passive"))
      (node (ref "R19") (pin "2") (pinfunction "2_2") (pintype "passive"))
    )
    (net (code "38") (name "Net-(C14-Pad1)") (class "Default")
      (node (ref "C14") (pin "1") (pinfunction "1_1") (pintype "passive"))
      (node (ref "R20") (pin "1") (pinfunction "1_1") (pintype "passive"))
      (node (ref "R21") (pin "2") (pinfunction "2_2") (pintype "passive"))
      (node (ref "R22") (pin "2") (pinfunction "2_2") (pintype "passive"))
    )
    (net (code "39") (name "Net-(C18-Pad1)") (class "Default")
      (node (ref "C18") (pin "1") (pinfunction "1_1") (pintype "passive"))
      (node (ref "R25") (pin "1") (pinfunction "1_1") (pintype "passive"))
      (node (ref "R26") (pin "2") (pinfunction "2_2") (pintype "passive"))
      (node (ref "R28") (pin "1") (pinfunction "1_1") (pintype "passive"))
    )
    (net (code "40") (name "Net-(CVX_L-3)") (class "Default")
      (node (ref "CVX_L") (pin "P$3") (pinfunction "3_P$3") (pintype "passive"))
      (node (ref "R8") (pin "1") (pinfunction "1_1") (pintype "passive"))
    )
    (net (code "41") (name "Net-(CVX_R-3)") (class "Default")
      (node (ref "CVX_R") (pin "P$3") (pinfunction "3_P$3") (pintype "passive"))
      (node (ref "R31") (pin "1") (pinfunction "1_1") (pintype "passive"))
    )
    (net (code "42") (name "Net-(CVY_L-3)") (class "Default")
      (node (ref "CVY_L") (pin "P$3") (pinfunction "3_P$3") (pintype "passive"))
      (node (ref "R33") (pin "1") (pinfunction "1_1") (pintype "passive"))
    )
    (net (code "43") (name "Net-(CVY_R-3)") (class "Default")
      (node (ref "CVY_R") (pin "P$3") (pinfunction "3_P$3") (pintype "passive"))
      (node (ref "R37") (pin "1") (pinfunction "1_1") (pintype "passive"))
    )
    (net (code "44") (name "Net-(D1-C1A2)") (class "Default")
      (node (ref "D1") (pin "3") (pinfunction "C1A2_3") (pintype "passive"))
      (node (ref "R39") (pin "2") (pinfunction "2_2") (pintype "passive"))
      (node (ref "R40") (pin "1") (pinfunction "1_1") (pintype "passive"))
    )
    (net (code "45") (name "Net-(D2-C1A2)") (class "Default")
      (node (ref "D2") (pin "3") (pinfunction "C1A2_3") (pintype "passive"))
      (node (ref "R41") (pin "2") (pinfunction "2_2") (pintype "passive"))
      (node (ref "R42") (pin "1") (pinfunction "1_1") (pintype "passive"))
    )
    (net (code "46") (name "Net-(D3-C1A2)") (class "Default")
      (node (ref "D3") (pin "3") (pinfunction "C1A2_3") (pintype "passive"))
      (node (ref "R46") (pin "2") (pinfunction "2_2") (pintype "passive"))
      (node (ref "R47") (pin "1") (pinfunction "1_1") (pintype "passive"))
    )
    (net (code "47") (name "Net-(D4-C1A2)") (class "Default")
      (node (ref "D4") (pin "3") (pinfunction "C1A2_3") (pintype "passive"))
      (node (ref "R51") (pin "2") (pinfunction "2_2") (pintype "passive"))
      (node (ref "R52") (pin "1") (pinfunction "1_1") (pintype "passive"))
    )
    (net (code "48") (name "Net-(D5-C1A2)") (class "Default")
      (node (ref "D5") (pin "3") (pinfunction "C1A2_3") (pintype "passive"))
      (node (ref "R57") (pin "1") (pinfunction "1_1") (pintype "passive"))
      (node (ref "R58") (pin "2") (pinfunction "2_2") (pintype "passive"))
    )
    (net (code "49") (name "Net-(D6-C1A2)") (class "Default")
      (node (ref "D6") (pin "3") (pinfunction "C1A2_3") (pintype "passive"))
      (node (ref "R62") (pin "1") (pinfunction "1_1") (pintype "passive"))
      (node (ref "R63") (pin "2") (pinfunction "2_2") (pintype "passive"))
    )
    (net (code "50") (name "Net-(FM_L-3)") (class "Default")
      (node (ref "FM_L") (pin "P$3") (pinfunction "3_P$3") (pintype "passive"))
      (node (ref "POTFM_L") (pin "3") (pinfunction "3_3") (pintype "bidirectional"))
    )
    (net (code "51") (name "Net-(FM_R-3)") (class "Default")
      (node (ref "FM_R") (pin "P$3") (pinfunction "3_P$3") (pintype "passive"))
      (node (ref "POTFM_R") (pin "3") (pinfunction "3_3") (pintype "bidirectional"))
    )
    (net (code "52") (name "Net-(IC2A-+IN)") (class "Default")
      (node (ref "IC2") (pin "3") (pinfunction "+IN_3") (pintype "input"))
      (node (ref "R3") (pin "2") (pinfunction "2_2") (pintype "passive"))
      (node (ref "R4") (pin "1") (pinfunction "1_1") (pintype "passive"))
    )
    (net (code "53") (name "Net-(IC2A--IN)") (class "Default")
      (node (ref "IC2") (pin "2") (pinfunction "-IN_2") (pintype "input"))
      (node (ref "R1") (pin "2") (pinfunction "2_2") (pintype "passive"))
      (node (ref "R2") (pin "1") (pinfunction "1_1") (pintype "passive"))
    )
    (net (code "54") (name "Net-(IC2A-OUT)") (class "Default")
      (node (ref "IC2") (pin "1") (pinfunction "OUT_1") (pintype "output"))
      (node (ref "R1") (pin "1") (pinfunction "1_1") (pintype "passive"))
      (node (ref "R7") (pin "2") (pinfunction "2_2") (pintype "passive"))
    )
    (net (code "55") (name "Net-(IC2B-+IN)") (class "Default")
      (node (ref "IC2") (pin "5") (pinfunction "+IN_5") (pintype "input"))
      (node (ref "R5") (pin "2") (pinfunction "2_2") (pintype "passive"))
      (node (ref "R6") (pin "1") (pinfunction "1_1") (pintype "passive"))
    )
    (net (code "56") (name "Net-(IC2B--IN)") (class "Default")
      (node (ref "IC2") (pin "6") (pinfunction "-IN_6") (pintype "input"))
      (node (ref "R11") (pin "2") (pinfunction "2_2") (pintype "passive"))
      (node (ref "R12") (pin "1") (pinfunction "1_1") (pintype "passive"))
    )
    (net (code "57") (name "Net-(IC2B-OUT)") (class "Default")
      (node (ref "IC2") (pin "7") (pinfunction "OUT_7") (pintype "output"))
      (node (ref "R10") (pin "2") (pinfunction "2_2") (pintype "passive"))
      (node (ref "R11") (pin "1") (pinfunction "1_1") (pintype "passive"))
    )
    (net (code "58") (name "Net-(IC3A-+IN)") (class "Default")
      (node (ref "C21") (pin "1") (pinfunction "1_1") (pintype "passive"))
      (node (ref "IC3") (pin "3") (pinfunction "+IN_3") (pintype "input"))
      (node (ref "R18") (pin "2") (pinfunction "2_2") (pintype "passive"))
    )
    (net (code "59") (name "Net-(IC3A--IN)") (class "Default")
      (node (ref "C11") (pin "1") (pinfunction "1_1") (pintype "passive"))
      (node (ref "IC3") (pin "2") (pinfunction "-IN_2") (pintype "input"))
      (node (ref "R15") (pin "2") (pinfunction "2_2") (pintype "passive"))
    )
    (net (code "60") (name "Net-(IC3A-OUT)") (class "Default")
      (node (ref "C11") (pin "2") (pinfunction "2_2") (pintype "passive"))
      (node (ref "IC3") (pin "1") (pinfunction "OUT_1") (pintype "output"))
      (node (ref "R13") (pin "1") (pinfunction "1_1") (pintype "passive"))
      (node (ref "R14") (pin "2") (pinfunction "2_2") (pintype "passive"))
    )
    (net (code "61") (name "Net-(IC3B-+IN)") (class "Default")
      (node (ref "C22") (pin "1") (pinfunction "1_1") (pintype "passive"))
      (node (ref "IC3") (pin "5") (pinfunction "+IN_5") (pintype "input"))
      (node (ref "R20") (pin "2") (pinfunction "2_2") (pintype "passive"))
    )
    (net (code "62") (name "Net-(IC3B--IN)") (class "Default")
      (node (ref "C16") (pin "1") (pinfunction "1_1") (pintype "passive"))
      (node (ref "IC3") (pin "6") (pinfunction "-IN_6") (pintype "input"))
      (node (ref "R25") (pin "2") (pinfunction "2_2") (pintype "passive"))
    )
    (net (code "63") (name "Net-(IC3B-OUT)") (class "Default")
      (node (ref "C16") (pin "2") (pinfunction "2_2") (pintype "passive"))
      (node (ref "IC3") (pin "7") (pinfunction "OUT_7") (pintype "output"))
      (node (ref "R27") (pin "1") (pinfunction "1_1") (pintype "passive"))
      (node (ref "R28") (pin "2") (pinfunction "2_2") (pintype "passive"))
    )
    (net (code "64") (name "Net-(IC4A--IN)") (class "Default")
      (node (ref "IC4") (pin "2") (pinfunction "-IN_2") (pintype "input"))
      (node (ref "R23") (pin "1") (pinfunction "1_1") (pintype "passive"))
      (node (ref "R8") (pin "2") (pinfunction "2_2") (pintype "passive"))
      (node (ref "R9") (pin "2") (pinfunction "2_2") (pintype "passive"))
    )
    (net (code "65") (name "Net-(IC4A-OUT)") (class "Default")
      (node (ref "IC4") (pin "1") (pinfunction "OUT_1") (pintype "output"))
      (node (ref "R23") (pin "2") (pinfunction "2_2") (pintype "passive"))
      (node (ref "R40") (pin "2") (pinfunction "2_2") (pintype "passive"))
    )
    (net (code "66") (name "Net-(IC4B--IN)") (class "Default")
      (node (ref "IC4") (pin "6") (pinfunction "-IN_6") (pintype "input"))
      (node (ref "R24") (pin "1") (pinfunction "1_1") (pintype "passive"))
      (node (ref "R31") (pin "2") (pinfunction "2_2") (pintype "passive"))
      (node (ref "R32") (pin "2") (pinfunction "2_2") (pintype "passive"))
    )
    (net (code "67") (name "Net-(IC4B-OUT)") (class "Default")
      (node (ref "IC4") (pin "7") (pinfunction "OUT_7") (pintype "output"))
      (node (ref "R24") (pin "2") (pinfunction "2_2") (pintype "passive"))
      (node (ref "R42") (pin "2") (pinfunction "2_2") (pintype "passive"))
    )
    (net (code "68") (name "Net-(IC4C--IN)") (class "Default")
      (node (ref "IC4") (pin "9") (pinfunction "-IN_9") (pintype "input"))
      (node (ref "R30") (pin "2") (pinfunction "2_2") (pintype "passive"))
      (node (ref "R33") (pin "2") (pinfunction "2_2") (pintype "passive"))
      (node (ref "R35") (pin "1") (pinfunction "1_1") (pintype "passive"))
    )
    (net (code "69") (name "Net-(IC4C-OUT)") (class "Default")
      (node (ref "IC4") (pin "8") (pinfunction "OUT_8") (pintype "output"))
      (node (ref "R35") (pin "2") (pinfunction "2_2") (pintype "passive"))
      (node (ref "R47") (pin "2") (pinfunction "2_2") (pintype "passive"))
    )
    (net (code "70") (name "Net-(IC4D--IN)") (class "Default")
      (node (ref "IC4") (pin "13") (pinfunction "-IN_13") (pintype "input"))
      (node (ref "R34") (pin "1") (pinfunction "1_1") (pintype "passive"))
      (node (ref "R37") (pin "2") (pinfunction "2_2") (pintype "passive"))
      (node (ref "R38") (pin "2") (pinfunction "2_2") (pintype "passive"))
    )
    (net (code "71") (name "Net-(IC4D-OUT)") (class "Default")
      (node (ref "IC4") (pin "14") (pinfunction "OUT_14") (pintype "output"))
      (node (ref "R34") (pin "2") (pinfunction "2_2") (pintype "passive"))
      (node (ref "R52") (pin "2") (pinfunction "2_2") (pintype "passive"))
    )
    (net (code "72") (name "Net-(IC6A--IN)") (class "Default")
      (node (ref "IC6") (pin "2") (pinfunction "-IN_2") (pintype "input"))
      (node (ref "R36") (pin "2") (pinfunction "2_2") (pintype "passive"))
      (node (ref "R54") (pin "2") (pinfunction "2_2") (pintype "passive"))
      (node (ref "R56") (pin "1") (pinfunction "1_1") (pintype "passive"))
    )
    (net (code "73") (name "Net-(IC6A-OUT)") (class "Default")
      (node (ref "IC6") (pin "1") (pinfunction "OUT_1") (pintype "output"))
      (node (ref "R56") (pin "2") (pinfunction "2_2") (pintype "passive"))
      (node (ref "R57") (pin "2") (pinfunction "2_2") (pintype "passive"))
    )
    (net (code "74") (name "Net-(IC6B--IN)") (class "Default")
      (node (ref "IC6") (pin "6") (pinfunction "-IN_6") (pintype "input"))
      (node (ref "R43") (pin "2") (pinfunction "2_2") (pintype "passive"))
      (node (ref "R59") (pin "2") (pinfunction "2_2") (pintype "passive"))
      (node (ref "R61") (pin "1") (pinfunction "1_1") (pintype "passive"))
    )
    (net (code "75") (name "Net-(IC6B-OUT)") (class "Default")
      (node (ref "IC6") (pin "7") (pinfunction "OUT_7") (pintype "output"))
      (node (ref "R61") (pin "2") (pinfunction "2_2") (pintype "passive"))
      (node (ref "R62") (pin "2") (pinfunction "2_2") (pintype "passive"))
    )
    (net (code "76") (name "Net-(POTFM_L-Pad2)") (class "Default")
      (node (ref "POTFM_L") (pin "2") (pinfunction "2_2") (pintype "bidirectional"))
      (node (ref "R54") (pin "1") (pinfunction "1_1") (pintype "passive"))
    )
    (net (code "77") (name "Net-(POTFM_R-Pad2)") (class "Default")
      (node (ref "POTFM_R") (pin "2") (pinfunction "2_2") (pintype "bidirectional"))
      (node (ref "R59") (pin "1") (pinfunction "1_1") (pintype "passive"))
    )
    (net (code "78") (name "Net-(POTX_L-Pad2)") (class "Default")
      (node (ref "POTX_L") (pin "2") (pinfunction "2_2") (pintype "bidirectional"))
      (node (ref "R9") (pin "1") (pinfunction "1_1") (pintype "passive"))
    )
    (net (code "79") (name "Net-(POTX_R-Pad2)") (class "Default")
      (node (ref "POTX_R") (pin "2") (pinfunction "2_2") (pintype "bidirectional"))
      (node (ref "R32") (pin "1") (pinfunction "1_1") (pintype "passive"))
    )
    (net (code "80") (name "Net-(POTY_L-Pad2)") (class "Default")
      (node (ref "POTY_L") (pin "2") (pinfunction "2_2") (pintype "bidirectional"))
      (node (ref "R30") (pin "1") (pinfunction "1_1") (pintype "passive"))
    )
    (net (code "81") (name "Net-(POTY_R-Pad2)") (class "Default")
      (node (ref "POTY_R") (pin "2") (pinfunction "2_2") (pintype "bidirectional"))
      (node (ref "R38") (pin "1") (pinfunction "1_1") (pintype "passive"))
    )
    (net (code "82") (name "Net-(Q1-D)") (class "Default")
      (node (ref "JP8") (pin "10") (pinfunction "10_10") (pintype "passive"))
      (node (ref "JP8") (pin "9") (pinfunction "9_9") (pintype "passive"))
      (node (ref "Q1") (pin "3") (pinfunction "D_3") (pintype "passive"))
    )
    (net (code "83") (name "Net-(Q2-D)") (class "Default")
      (node (ref "JP8") (pin "1") (pinfunction "1_1") (pintype "passive"))
      (node (ref "JP8") (pin "2") (pinfunction "2_2") (pintype "passive"))
      (node (ref "Q2") (pin "3") (pinfunction "D_3") (pintype "passive"))
    )
    (net (code "84") (name "unconnected-(LGP1-5-Pad1)") (class "Default")
      (node (ref "LGP1-5") (pin "1") (pinfunction "1_1") (pintype "passive"))
    )
    (net (code "85") (name "unconnected-(LGP1-5-Pad2)") (class "Default")
      (node (ref "LGP1-5") (pin "2") (pinfunction "2_2") (pintype "passive"))
    )
    (net (code "86") (name "unconnected-(LGP1-5-Pad5)") (class "Default")
      (node (ref "LGP1-5") (pin "5") (pinfunction "5_5") (pintype "passive"))
    )
    (net (code "87") (name "unconnected-(LGP6-7-Pad1)") (class "Default")
      (node (ref "LGP6-7") (pin "1") (pinfunction "1_1") (pintype "passive"))
    )
    (net (code "88") (name "unconnected-(LGP6-7-Pad2)") (class "Default")
      (node (ref "LGP6-7") (pin "2") (pinfunction "2_2") (pintype "passive"))
    )
    (net (code "89") (name "unconnected-(OUT_L-4-PadP$2)") (class "Default")
      (node (ref "OUT_L") (pin "P$2") (pinfunction "4_P$2") (pintype "passive"))
    )
    (net (code "90") (name "unconnected-(OUT_R-4-PadP$2)") (class "Default")
      (node (ref "OUT_R") (pin "P$2") (pinfunction "4_P$2") (pintype "passive"))
    )
    (net (code "91") (name "unconnected-(TGP1-4-Pad1)") (class "Default")
      (node (ref "TGP1-4") (pin "1") (pinfunction "1_1") (pintype "passive"))
    )
    (net (code "92") (name "unconnected-(TGP1-4-Pad2)") (class "Default")
      (node (ref "TGP1-4") (pin "2") (pinfunction "2_2") (pintype "passive"))
    )
    (net (code "93") (name "unconnected-(TGP1-4-Pad4)") (class "Default")
      (node (ref "TGP1-4") (pin "4") (pinfunction "4_4") (pintype "passive"))
    )
    (net (code "94") (name "unconnected-(TGP1-4-Pad5)") (class "Default")
      (node (ref "TGP1-4") (pin "5") (pinfunction "5_5") (pintype "passive"))
    )
  )
)
